# Power-Bus.net
KiCad netlist of a schematic drawn in EAGLE
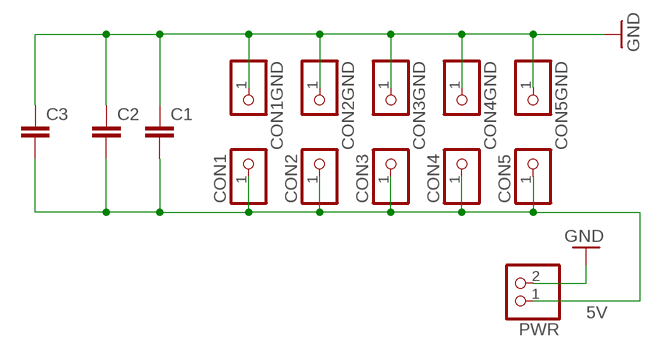
[diagram p0: schematic, sheet 1]

(export (version "E")
  (design (tool "Eeschema 10.0.6"))
  (components
    (comp (ref "C1")
      (value "C-EU050-025X075")
      (footprint "eagle-import:C050-025X075")
      (libsource (lib "eagle-import") (part "C-EU050-025X075"))
    )
    (comp (ref "C2")
      (value "C-EU050-025X075")
      (footprint "eagle-import:C050-025X075")
      (libsource (lib "eagle-import") (part "C-EU050-025X075"))
    )
    (comp (ref "C3")
      (value "C-EU050-025X075")
      (footprint "eagle-import:C050-025X075")
      (libsource (lib "eagle-import") (part "C-EU050-025X075"))
    )
    (comp (ref "CON1")
      (value "PINHD-1X1")
      (footprint "eagle-import:1X01")
      (libsource (lib "eagle-import") (part "PINHD-1X1"))
    )
    (comp (ref "CON1GND")
      (value "PINHD-1X1")
      (footprint "eagle-import:1X01")
      (libsource (lib "eagle-import") (part "PINHD-1X1"))
    )
    (comp (ref "CON2")
      (value "PINHD-1X1")
      (footprint "eagle-import:1X01")
      (libsource (lib "eagle-import") (part "PINHD-1X1"))
    )
    (comp (ref "CON2GND")
      (value "PINHD-1X1")
      (footprint "eagle-import:1X01")
      (libsource (lib "eagle-import") (part "PINHD-1X1"))
    )
    (comp (ref "CON3")
      (value "PINHD-1X1")
      (footprint "eagle-import:1X01")
      (libsource (lib "eagle-import") (part "PINHD-1X1"))
    )
    (comp (ref "CON3GND")
      (value "PINHD-1X1")
      (footprint "eagle-import:1X01")
      (libsource (lib "eagle-import") (part "PINHD-1X1"))
    )
    (comp (ref "CON4")
      (value "PINHD-1X1")
      (footprint "eagle-import:1X01")
      (libsource (lib "eagle-import") (part "PINHD-1X1"))
    )
    (comp (ref "CON4GND")
      (value "PINHD-1X1")
      (footprint "eagle-import:1X01")
      (libsource (lib "eagle-import") (part "PINHD-1X1"))
    )
    (comp (ref "CON5")
      (value "PINHD-1X1")
      (footprint "eagle-import:1X01")
      (libsource (lib "eagle-import") (part "PINHD-1X1"))
    )
    (comp (ref "CON5GND")
      (value "PINHD-1X1")
      (footprint "eagle-import:1X01")
      (libsource (lib "eagle-import") (part "PINHD-1X1"))
    )
    (comp (ref "PWR")
      (value "PINHD-1X2/90")
      (footprint "eagle-import:1X02_90")
      (libsource (lib "eagle-import") (part "PINHD-1X2/90"))
    )
  )
  (nets
    (net (code "1") (name "/5V") (class "Default")
      (node (ref "C1") (pin "2") (pinfunction "2_2") (pintype "passive"))
      (node (ref "C2") (pin "2") (pinfunction "2_2") (pintype "passive"))
      (node (ref "C3") (pin "2") (pinfunction "2_2") (pintype "passive"))
      (node (ref "CON1") (pin "1") (pinfunction "1_1") (pintype "passive"))
      (node (ref "CON2") (pin "1") (pinfunction "1_1") (pintype "passive"))
      (node (ref "CON3") (pin "1") (pinfunction "1_1") (pintype "passive"))
      (node (ref "CON4") (pin "1") (pinfunction "1_1") (pintype "passive"))
      (node (ref "CON5") (pin "1") (pinfunction "1_1") (pintype "passive"))
      (node (ref "PWR") (pin "1") (pinfunction "1_1") (pintype "passive"))
    )
    (net (code "2") (name "GND") (class "Default")
      (node (ref "C1") (pin "1") (pinfunction "1_1") (pintype "passive"))
      (node (ref "C2") (pin "1") (pinfunction "1_1") (pintype "passive"))
      (node (ref "C3") (pin "1") (pinfunction "1_1") (pintype "passive"))
      (node (ref "CON1GND") (pin "1") (pinfunction "1_1") (pintype "passive"))
      (node (ref "CON2GND") (pin "1") (pinfunction "1_1") (pintype "passive"))
      (node (ref "CON3GND") (pin "1") (pinfunction "1_1") (pintype "passive"))
      (node (ref "CON4GND") (pin "1") (pinfunction "1_1") (pintype "passive"))
      (node (ref "CON5GND") (pin "1") (pinfunction "1_1") (pintype "passive"))
      (node (ref "PWR") (pin "2") (pinfunction "2_2") (pintype "passive"))
    )
  )
)
